# ece521oscillator.net
KiCad netlist of a schematic drawn in EAGLE
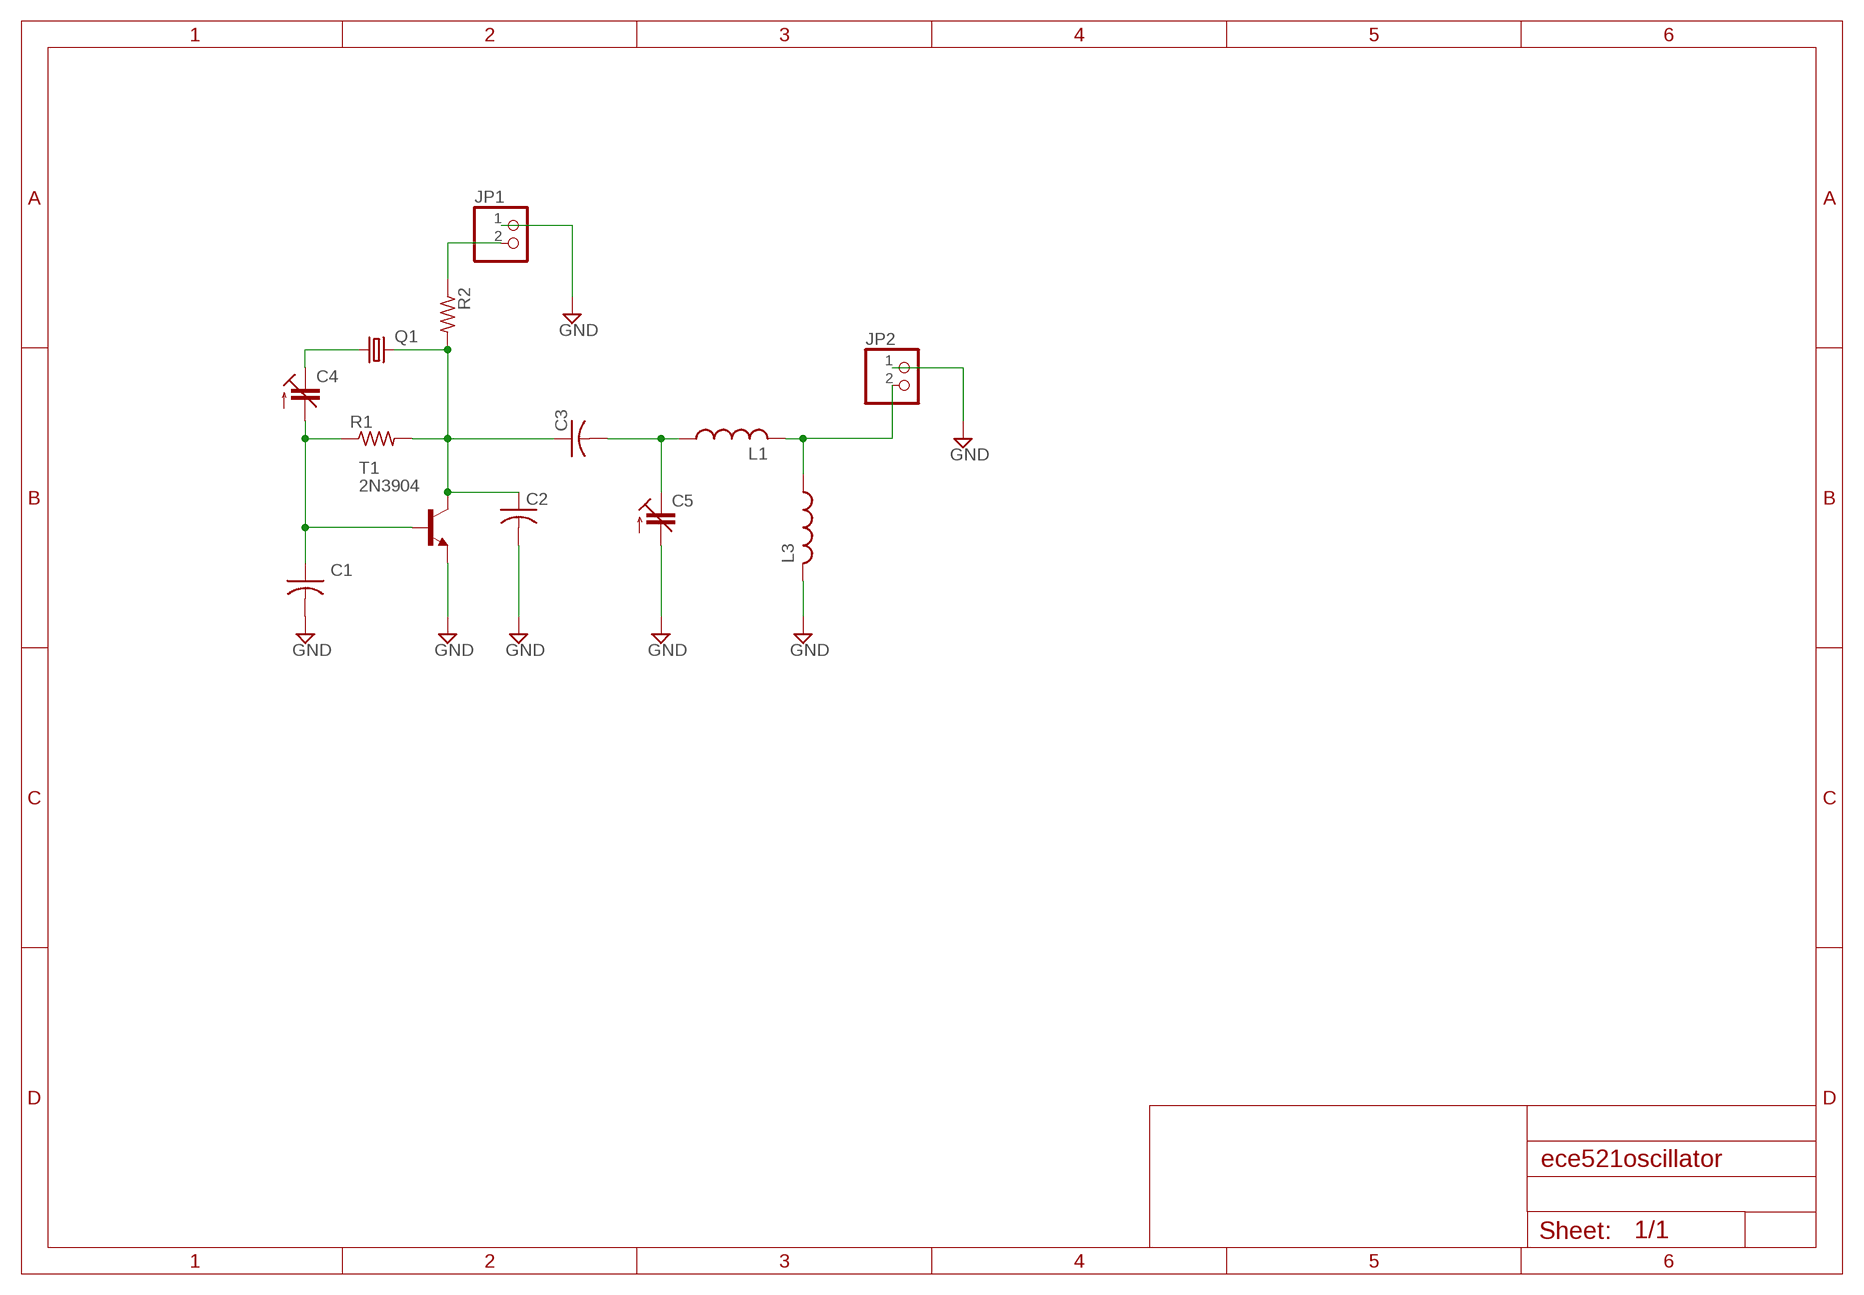
[diagram p0: schematic, sheet 1]

(export (version "E")
  (design (tool "Eeschema 10.0.6"))
  (components
    (comp (ref "C1")
      (value "C-US050-025X075")
      (footprint "eagle-import:C050-025X075")
      (libsource (lib "eagle-import") (part "C-US050-025X075"))
    )
    (comp (ref "C2")
      (value "C-US050-025X075")
      (footprint "eagle-import:C050-025X075")
      (libsource (lib "eagle-import") (part "C-US050-025X075"))
    )
    (comp (ref "C3")
      (value "C-US050-025X075")
      (footprint "eagle-import:C050-025X075")
      (libsource (lib "eagle-import") (part "C-US050-025X075"))
    )
    (comp (ref "C4")
      (value "C-TRIMM808")
      (footprint "eagle-import:CTRIM808-BC")
      (libsource (lib "eagle-import") (part "C-TRIMM808"))
    )
    (comp (ref "C5")
      (value "C-TRIMM808")
      (footprint "eagle-import:CTRIM808-BC")
      (libsource (lib "eagle-import") (part "C-TRIMM808"))
    )
    (comp (ref "JP1")
      (value "PINHD-1X2")
      (footprint "eagle-import:1X02")
      (libsource (lib "eagle-import") (part "PINHD-1X2"))
    )
    (comp (ref "JP2")
      (value "PINHD-1X2")
      (footprint "eagle-import:1X02")
      (libsource (lib "eagle-import") (part "PINHD-1X2"))
    )
    (comp (ref "L1")
      (value "L-US0204/7")
      (footprint "eagle-import:0204_7")
      (libsource (lib "eagle-import") (part "L-US0204/7"))
    )
    (comp (ref "L3")
      (value "L-US0204/7")
      (footprint "eagle-import:0204_7")
      (libsource (lib "eagle-import") (part "L-US0204/7"))
    )
    (comp (ref "Q1")
      (value "CRYSTALHC18U-V")
      (footprint "eagle-import:HC18U-V")
      (libsource (lib "eagle-import") (part "CRYSTALHC18U-V"))
    )
    (comp (ref "R1")
      (value "R-US_0204/7")
      (footprint "eagle-import:0204_7")
      (libsource (lib "eagle-import") (part "R-US_0204/7"))
    )
    (comp (ref "R2")
      (value "R-US_0204/7")
      (footprint "eagle-import:0204_7")
      (libsource (lib "eagle-import") (part "R-US_0204/7"))
    )
    (comp (ref "T1")
      (value "2N3904")
      (footprint "eagle-import:TO92")
      (libsource (lib "eagle-import") (part "2N3904"))
    )
  )
  (nets
    (net (code "1") (name "GND") (class "Default")
      (node (ref "C1") (pin "2") (pinfunction "2_2") (pintype "passive"))
      (node (ref "C2") (pin "2") (pinfunction "2_2") (pintype "passive"))
      (node (ref "C5") (pin "2") (pinfunction "A_2") (pintype "passive"))
      (node (ref "JP1") (pin "1") (pinfunction "1_1") (pintype "passive"))
      (node (ref "JP2") (pin "1") (pinfunction "1_1") (pintype "passive"))
      (node (ref "L3") (pin "2") (pinfunction "2_2") (pintype "passive"))
      (node (ref "T1") (pin "3") (pinfunction "E_3") (pintype "passive"))
    )
    (net (code "2") (name "Net-(C4-A)") (class "Default")
      (node (ref "C1") (pin "1") (pinfunction "1_1") (pintype "passive"))
      (node (ref "C4") (pin "2") (pinfunction "A_2") (pintype "passive"))
      (node (ref "R1") (pin "1") (pinfunction "1_1") (pintype "passive"))
      (node (ref "T1") (pin "2") (pinfunction "B_2") (pintype "passive"))
    )
    (net (code "3") (name "Net-(C4-E)") (class "Default")
      (node (ref "C4") (pin "1") (pinfunction "E_1") (pintype "passive"))
      (node (ref "Q1") (pin "1") (pinfunction "1_1") (pintype "passive"))
    )
    (net (code "4") (name "Net-(C5-E)") (class "Default")
      (node (ref "C3") (pin "2") (pinfunction "2_2") (pintype "passive"))
      (node (ref "C5") (pin "1") (pinfunction "E_1") (pintype "passive"))
      (node (ref "L1") (pin "1") (pinfunction "1_1") (pintype "passive"))
    )
    (net (code "5") (name "Net-(JP1-Pad2)") (class "Default")
      (node (ref "JP1") (pin "2") (pinfunction "2_2") (pintype "passive"))
      (node (ref "R2") (pin "1") (pinfunction "1_1") (pintype "passive"))
    )
    (net (code "6") (name "Net-(JP2-Pad2)") (class "Default")
      (node (ref "JP2") (pin "2") (pinfunction "2_2") (pintype "passive"))
      (node (ref "L1") (pin "2") (pinfunction "2_2") (pintype "passive"))
      (node (ref "L3") (pin "1") (pinfunction "1_1") (pintype "passive"))
    )
    (net (code "7") (name "Net-(T1-C)") (class "Default")
      (node (ref "C2") (pin "1") (pinfunction "1_1") (pintype "passive"))
      (node (ref "C3") (pin "1") (pinfunction "1_1") (pintype "passive"))
      (node (ref "Q1") (pin "2") (pinfunction "2_2") (pintype "passive"))
      (node (ref "R1") (pin "2") (pinfunction "2_2") (pintype "passive"))
      (node (ref "R2") (pin "2") (pinfunction "2_2") (pintype "passive"))
      (node (ref "T1") (pin "1") (pinfunction "C_1") (pintype "passive"))
    )
  )
)
